# MetronomeSMD.net
KiCad netlist of a schematic drawn in EAGLE
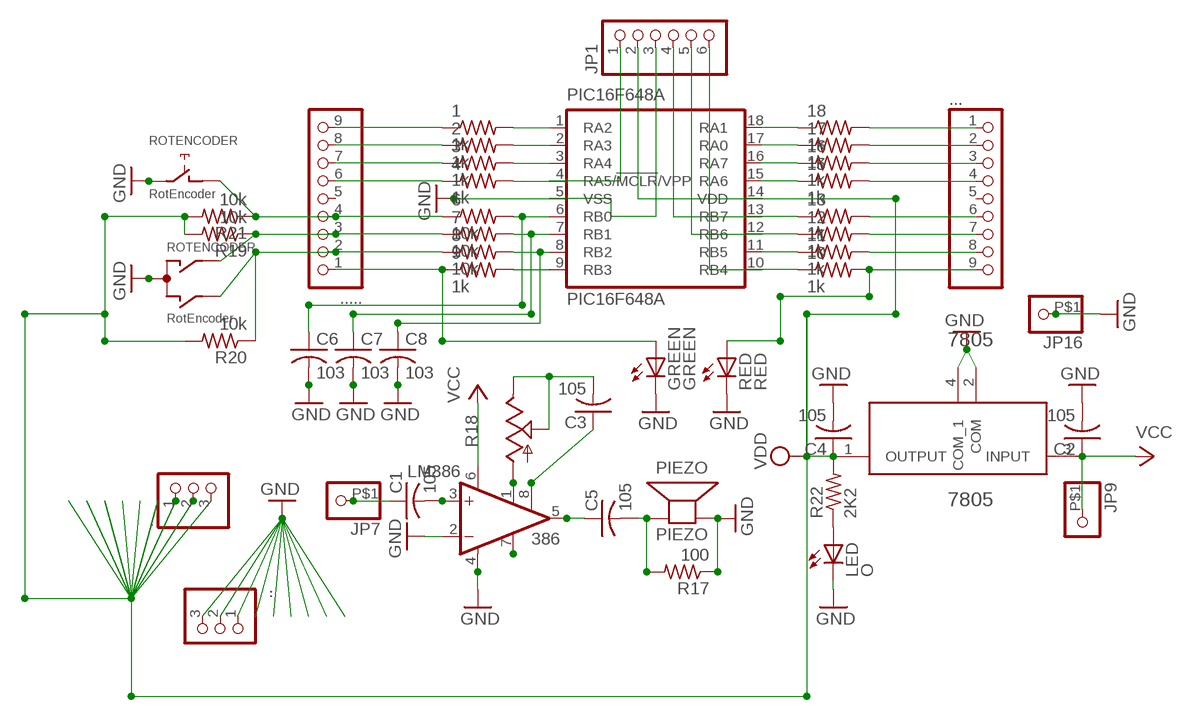
[diagram p0: schematic, sheet 1]

(export (version "E")
  (design (tool "Eeschema 10.0.6"))
  (components
    (comp (ref ".")
      (value "PINHD-1X3CB")
      (footprint "eagle-import:1X03-CLEANBIG")
      (libsource (lib "eagle-import") (part "PINHD-1X3CB"))
    )
    (comp (ref "..")
      (value "PINHD-1X3CB")
      (footprint "eagle-import:1X03-CLEANBIG")
      (libsource (lib "eagle-import") (part "PINHD-1X3CB"))
    )
    (comp (ref "...")
      (value "PINHD-1X9")
      (footprint "eagle-import:1X09-BIG")
      (libsource (lib "eagle-import") (part "PINHD-1X9"))
    )
    (comp (ref ".....")
      (value "PINHD-1X9")
      (footprint "eagle-import:1X09-BIG")
      (libsource (lib "eagle-import") (part "PINHD-1X9"))
    )
    (comp (ref "1")
      (value "1k")
      (footprint "eagle-import:R1206")
      (libsource (lib "eagle-import") (part "R-US_R1206"))
    )
    (comp (ref "2")
      (value "1k")
      (footprint "eagle-import:R1206")
      (libsource (lib "eagle-import") (part "R-US_R1206"))
    )
    (comp (ref "3")
      (value "1k")
      (footprint "eagle-import:R1206")
      (libsource (lib "eagle-import") (part "R-US_R1206"))
    )
    (comp (ref "4")
      (value "1k")
      (footprint "eagle-import:R1206")
      (libsource (lib "eagle-import") (part "R-US_R1206"))
    )
    (comp (ref "6")
      (value "10k")
      (footprint "eagle-import:R1206")
      (libsource (lib "eagle-import") (part "R-US_R1206"))
    )
    (comp (ref "7")
      (value "10k")
      (footprint "eagle-import:R1206")
      (libsource (lib "eagle-import") (part "R-US_R1206"))
    )
    (comp (ref "8")
      (value "10k")
      (footprint "eagle-import:R1206")
      (libsource (lib "eagle-import") (part "R-US_R1206"))
    )
    (comp (ref "9")
      (value "1k")
      (footprint "eagle-import:R1206")
      (libsource (lib "eagle-import") (part "R-US_R1206"))
    )
    (comp (ref "10")
      (value "1k")
      (footprint "eagle-import:R1206")
      (libsource (lib "eagle-import") (part "R-US_R1206"))
    )
    (comp (ref "11")
      (value "1k")
      (footprint "eagle-import:R1206")
      (libsource (lib "eagle-import") (part "R-US_R1206"))
    )
    (comp (ref "12")
      (value "1k")
      (footprint "eagle-import:R1206")
      (libsource (lib "eagle-import") (part "R-US_R1206"))
    )
    (comp (ref "13")
      (value "1k")
      (footprint "eagle-import:R1206")
      (libsource (lib "eagle-import") (part "R-US_R1206"))
    )
    (comp (ref "15")
      (value "1k")
      (footprint "eagle-import:R1206")
      (libsource (lib "eagle-import") (part "R-US_R1206"))
    )
    (comp (ref "16")
      (value "1k")
      (footprint "eagle-import:R1206")
      (libsource (lib "eagle-import") (part "R-US_R1206"))
    )
    (comp (ref "17")
      (value "1k")
      (footprint "eagle-import:R1206")
      (libsource (lib "eagle-import") (part "R-US_R1206"))
    )
    (comp (ref "18")
      (value "1k")
      (footprint "eagle-import:R1206")
      (libsource (lib "eagle-import") (part "R-US_R1206"))
    )
    (comp (ref "7805")
      (value "7805")
      (footprint "eagle-import:SOT150P400X160-4N")
      (fields (field (name "MPN") "UA78L05ACPKG3"))
      (libsource (lib "eagle-import") (part "UA78L05ACPKG3"))
    )
    (comp (ref "C1")
      (value "105")
      (footprint "eagle-import:C1210")
      (libsource (lib "eagle-import") (part "C-USC1210"))
    )
    (comp (ref "C2")
      (value "105")
      (footprint "eagle-import:C1210")
      (libsource (lib "eagle-import") (part "C-USC1210"))
    )
    (comp (ref "C3")
      (value "105")
      (footprint "eagle-import:C1210")
      (libsource (lib "eagle-import") (part "C-USC1210"))
    )
    (comp (ref "C4")
      (value "105")
      (footprint "eagle-import:C1210")
      (libsource (lib "eagle-import") (part "C-USC1210"))
    )
    (comp (ref "C5")
      (value "105")
      (footprint "eagle-import:C1210")
      (libsource (lib "eagle-import") (part "C-USC1210"))
    )
    (comp (ref "C6")
      (value "103")
      (footprint "eagle-import:C1210")
      (libsource (lib "eagle-import") (part "C-USC1210"))
    )
    (comp (ref "C7")
      (value "103")
      (footprint "eagle-import:C1210")
      (libsource (lib "eagle-import") (part "C-USC1210"))
    )
    (comp (ref "C8")
      (value "103")
      (footprint "eagle-import:C1210")
      (libsource (lib "eagle-import") (part "C-USC1210"))
    )
    (comp (ref "GREEN")
      (value "GREEN")
      (footprint "eagle-import:LED5MM")
      (libsource (lib "eagle-import") (part "LED5MM"))
    )
    (comp (ref "JP1")
      (value "PINHD-1X6LOCK")
      (footprint "eagle-import:1X06-BIGLOCK")
      (libsource (lib "eagle-import") (part "PINHD-1X6LOCK"))
    )
    (comp (ref "JP7")
      (value "PINHD-1X1-BIGPOGO")
      (footprint "eagle-import:1X1-BIGPOGO")
      (libsource (lib "eagle-import") (part "PINHD-1X1-BIGPOGO"))
    )
    (comp (ref "JP9")
      (value "PINHD-1X1-BIGPOGO")
      (footprint "eagle-import:1X1-BIGPOGO")
      (libsource (lib "eagle-import") (part "PINHD-1X1-BIGPOGO"))
    )
    (comp (ref "JP16")
      (value "PINHD-1X1-BIGPOGO")
      (footprint "eagle-import:1X1-BIGPOGO")
      (libsource (lib "eagle-import") (part "PINHD-1X1-BIGPOGO"))
    )
    (comp (ref "LED")
      (value "O")
      (footprint "eagle-import:CHIPLED_1206")
      (libsource (lib "eagle-import") (part "LEDCHIPLED_1206"))
    )
    (comp (ref "LM386")
      (value "386")
      (footprint "eagle-import:SO08")
      (libsource (lib "eagle-import") (part "LM386?-M1"))
    )
    (comp (ref "PIC16F648A")
      (value "PIC16F648A")
      (footprint "eagle-import:DIL18")
      (libsource (lib "eagle-import") (part "PIC16F1826/27P"))
    )
    (comp (ref "PIEZO")
      (value "PIEZO")
      (footprint "eagle-import:PS12")
      (libsource (lib "eagle-import") (part "SPEAKER/PS12"))
    )
    (comp (ref "R17")
      (value "100")
      (footprint "eagle-import:R1206")
      (libsource (lib "eagle-import") (part "R-US_R1206"))
    )
    (comp (ref "R18")
      (value "TRIM_US-RJ9W")
      (footprint "eagle-import:RJ9W")
      (libsource (lib "eagle-import") (part "TRIM_US-RJ9W"))
    )
    (comp (ref "R19")
      (value "10k")
      (footprint "eagle-import:R1206")
      (libsource (lib "eagle-import") (part "R-US_R1206"))
    )
    (comp (ref "R20")
      (value "10k")
      (footprint "eagle-import:R1206")
      (libsource (lib "eagle-import") (part "R-US_R1206"))
    )
    (comp (ref "R21")
      (value "10k")
      (footprint "eagle-import:R1206")
      (libsource (lib "eagle-import") (part "R-US_R1206"))
    )
    (comp (ref "R22")
      (value "2K2")
      (footprint "eagle-import:R1206")
      (libsource (lib "eagle-import") (part "R-US_R1206"))
    )
    (comp (ref "RED")
      (value "RED")
      (footprint "eagle-import:LED5MM")
      (libsource (lib "eagle-import") (part "LED5MM"))
    )
    (comp (ref "ROTENCODER")
      (value "RotEncoder")
      (footprint "eagle-import:ALPS_EC12E_SW")
      (fields (field (name "MPN") "EC12E2424407"))
      (libsource (lib "eagle-import") (part "EC12E_SW"))
    )
  )
  (nets
    (net (code "1") (name "GND") (class "Default")
      (node (ref "..") (pin "1") (pinfunction "1_1") (pintype "passive"))
      (node (ref "..") (pin "2") (pinfunction "2_2") (pintype "passive"))
      (node (ref "..") (pin "3") (pinfunction "3_3") (pintype "passive"))
      (node (ref "7805") (pin "2") (pinfunction "COM_2") (pintype "power_in"))
      (node (ref "7805") (pin "4") (pinfunction "COM_1_4") (pintype "power_in"))
      (node (ref "C2") (pin "2") (pinfunction "2_2") (pintype "passive"))
      (node (ref "C4") (pin "2") (pinfunction "2_2") (pintype "passive"))
      (node (ref "C6") (pin "2") (pinfunction "2_2") (pintype "passive"))
      (node (ref "C7") (pin "2") (pinfunction "2_2") (pintype "passive"))
      (node (ref "C8") (pin "2") (pinfunction "2_2") (pintype "passive"))
      (node (ref "GREEN") (pin "K") (pinfunction "C_K") (pintype "passive"))
      (node (ref "JP1") (pin "3") (pinfunction "3_3") (pintype "passive"))
      (node (ref "JP16") (pin "P$1") (pinfunction "1_P$1") (pintype "passive"))
      (node (ref "LED") (pin "C") (pinfunction "C_C") (pintype "passive"))
      (node (ref "LM386") (pin "2") (pinfunction "-IN_2") (pintype "input"))
      (node (ref "LM386") (pin "4") (pinfunction "GND_4") (pintype "power_in"))
      (node (ref "PIC16F648A") (pin "5") (pinfunction "VSS_5") (pintype "power_in"))
      (node (ref "PIEZO") (pin "P$2") (pinfunction "-_P$2") (pintype "passive"))
      (node (ref "R17") (pin "1") (pinfunction "1_1") (pintype "passive"))
      (node (ref "RED") (pin "K") (pinfunction "C_K") (pintype "passive"))
      (node (ref "ROTENCODER") (pin "C") (pinfunction "C_C") (pintype "passive"))
      (node (ref "ROTENCODER") (pin "E") (pinfunction "2_E") (pintype "passive"))
    )
    (net (code "2") (name "Net-(...-Pad1)") (class "Default")
      (node (ref "...") (pin "1") (pinfunction "1_1") (pintype "passive"))
      (node (ref "18") (pin "2") (pinfunction "2_2") (pintype "passive"))
    )
    (net (code "3") (name "Net-(...-Pad2)") (class "Default")
      (node (ref "...") (pin "2") (pinfunction "2_2") (pintype "passive"))
      (node (ref "17") (pin "2") (pinfunction "2_2") (pintype "passive"))
    )
    (net (code "4") (name "Net-(...-Pad3)") (class "Default")
      (node (ref "...") (pin "3") (pinfunction "3_3") (pintype "passive"))
      (node (ref "16") (pin "2") (pinfunction "2_2") (pintype "passive"))
    )
    (net (code "5") (name "Net-(...-Pad4)") (class "Default")
      (node (ref "...") (pin "4") (pinfunction "4_4") (pintype "passive"))
      (node (ref "15") (pin "2") (pinfunction "2_2") (pintype "passive"))
    )
    (net (code "6") (name "Net-(...-Pad6)") (class "Default")
      (node (ref "...") (pin "6") (pinfunction "6_6") (pintype "passive"))
      (node (ref "13") (pin "2") (pinfunction "2_2") (pintype "passive"))
    )
    (net (code "7") (name "Net-(...-Pad7)") (class "Default")
      (node (ref "...") (pin "7") (pinfunction "7_7") (pintype "passive"))
      (node (ref "12") (pin "2") (pinfunction "2_2") (pintype "passive"))
    )
    (net (code "8") (name "Net-(...-Pad8)") (class "Default")
      (node (ref "...") (pin "8") (pinfunction "8_8") (pintype "passive"))
      (node (ref "11") (pin "2") (pinfunction "2_2") (pintype "passive"))
    )
    (net (code "9") (name "Net-(...-Pad9)") (class "Default")
      (node (ref "...") (pin "9") (pinfunction "9_9") (pintype "passive"))
      (node (ref "10") (pin "2") (pinfunction "2_2") (pintype "passive"))
      (node (ref "RED") (pin "A") (pinfunction "A_A") (pintype "passive"))
    )
    (net (code "10") (name "Net-(.....-Pad1)") (class "Default")
      (node (ref ".....") (pin "1") (pinfunction "1_1") (pintype "passive"))
      (node (ref "9") (pin "1") (pinfunction "1_1") (pintype "passive"))
      (node (ref "GREEN") (pin "A") (pinfunction "A_A") (pintype "passive"))
    )
    (net (code "11") (name "Net-(.....-Pad2)") (class "Default")
      (node (ref ".....") (pin "2") (pinfunction "2_2") (pintype "passive"))
      (node (ref "8") (pin "1") (pinfunction "1_1") (pintype "passive"))
      (node (ref "R20") (pin "1") (pinfunction "1_1") (pintype "passive"))
      (node (ref "ROTENCODER") (pin "B") (pinfunction "B_B") (pintype "passive"))
    )
    (net (code "12") (name "Net-(.....-Pad3)") (class "Default")
      (node (ref ".....") (pin "3") (pinfunction "3_3") (pintype "passive"))
      (node (ref "7") (pin "1") (pinfunction "1_1") (pintype "passive"))
      (node (ref "R19") (pin "1") (pinfunction "1_1") (pintype "passive"))
      (node (ref "ROTENCODER") (pin "A") (pinfunction "A_A") (pintype "passive"))
    )
    (net (code "13") (name "Net-(.....-Pad6)") (class "Default")
      (node (ref ".....") (pin "6") (pinfunction "6_6") (pintype "passive"))
      (node (ref "4") (pin "1") (pinfunction "1_1") (pintype "passive"))
    )
    (net (code "14") (name "Net-(.....-Pad7)") (class "Default")
      (node (ref ".....") (pin "7") (pinfunction "7_7") (pintype "passive"))
      (node (ref "3") (pin "1") (pinfunction "1_1") (pintype "passive"))
    )
    (net (code "15") (name "Net-(.....-Pad8)") (class "Default")
      (node (ref ".....") (pin "8") (pinfunction "8_8") (pintype "passive"))
      (node (ref "2") (pin "1") (pinfunction "1_1") (pintype "passive"))
    )
    (net (code "16") (name "Net-(.....-Pad9)") (class "Default")
      (node (ref ".....") (pin "9") (pinfunction "9_9") (pintype "passive"))
      (node (ref "1") (pin "1") (pinfunction "1_1") (pintype "passive"))
    )
    (net (code "17") (name "Net-(C3-Pad1)") (class "Default")
      (node (ref "C3") (pin "1") (pinfunction "1_1") (pintype "passive"))
      (node (ref "LM386") (pin "8") (pinfunction "GAIN_8") (pintype "passive"))
    )
    (net (code "18") (name "Net-(C3-Pad2)") (class "Default")
      (node (ref "C3") (pin "2") (pinfunction "2_2") (pintype "passive"))
      (node (ref "R18") (pin "E") (pinfunction "E_E") (pintype "passive"))
      (node (ref "R18") (pin "S") (pinfunction "S_S") (pintype "passive"))
    )
    (net (code "19") (name "Net-(JP7-1)") (class "Default")
      (node (ref "C1") (pin "1") (pinfunction "1_1") (pintype "passive"))
      (node (ref "JP7") (pin "P$1") (pinfunction "1_P$1") (pintype "passive"))
    )
    (net (code "20") (name "Net-(LED-PadA)") (class "Default")
      (node (ref "LED") (pin "A") (pinfunction "A_A") (pintype "passive"))
      (node (ref "R22") (pin "1") (pinfunction "1_1") (pintype "passive"))
    )
    (net (code "21") (name "Net-(LM386-+IN)") (class "Default")
      (node (ref "C1") (pin "2") (pinfunction "2_2") (pintype "passive"))
      (node (ref "LM386") (pin "3") (pinfunction "+IN_3") (pintype "input"))
    )
    (net (code "22") (name "Net-(LM386-GAIN-Pad1)") (class "Default")
      (node (ref "LM386") (pin "1") (pinfunction "GAIN_1") (pintype "passive"))
      (node (ref "R18") (pin "A") (pinfunction "A_A") (pintype "passive"))
    )
    (net (code "23") (name "Net-(LM386-OUT)") (class "Default")
      (node (ref "C5") (pin "1") (pinfunction "1_1") (pintype "passive"))
      (node (ref "LM386") (pin "5") (pinfunction "OUT_5") (pintype "output"))
    )
    (net (code "24") (name "Net-(PIC16F648A-RA0)") (class "Default")
      (node (ref "17") (pin "1") (pinfunction "1_1") (pintype "passive"))
      (node (ref "PIC16F648A") (pin "17") (pinfunction "RA0_17") (pintype "bidirectional"))
    )
    (net (code "25") (name "Net-(PIC16F648A-RA1)") (class "Default")
      (node (ref "18") (pin "1") (pinfunction "1_1") (pintype "passive"))
      (node (ref "PIC16F648A") (pin "18") (pinfunction "RA1_18") (pintype "bidirectional"))
    )
    (net (code "26") (name "Net-(PIC16F648A-RA2)") (class "Default")
      (node (ref "1") (pin "2") (pinfunction "2_2") (pintype "passive"))
      (node (ref "PIC16F648A") (pin "1") (pinfunction "RA2_1") (pintype "bidirectional"))
    )
    (net (code "27") (name "Net-(PIC16F648A-RA3)") (class "Default")
      (node (ref "2") (pin "2") (pinfunction "2_2") (pintype "passive"))
      (node (ref "PIC16F648A") (pin "2") (pinfunction "RA3_2") (pintype "bidirectional"))
    )
    (net (code "28") (name "Net-(PIC16F648A-RA4)") (class "Default")
      (node (ref "3") (pin "2") (pinfunction "2_2") (pintype "passive"))
      (node (ref "PIC16F648A") (pin "3") (pinfunction "RA4_3") (pintype "bidirectional"))
    )
    (net (code "29") (name "Net-(PIC16F648A-RA5{slash}~{MCLR}{slash}VPP)") (class "Default")
      (node (ref "4") (pin "2") (pinfunction "2_2") (pintype "passive"))
      (node (ref "JP1") (pin "1") (pinfunction "1_1") (pintype "passive"))
      (node (ref "PIC16F648A") (pin "4") (pinfunction "RA5/~{MCLR}/VPP_4") (pintype "bidirectional"))
    )
    (net (code "30") (name "Net-(PIC16F648A-RA6)") (class "Default")
      (node (ref "15") (pin "1") (pinfunction "1_1") (pintype "passive"))
      (node (ref "PIC16F648A") (pin "15") (pinfunction "RA6_15") (pintype "bidirectional"))
    )
    (net (code "31") (name "Net-(PIC16F648A-RA7)") (class "Default")
      (node (ref "16") (pin "1") (pinfunction "1_1") (pintype "passive"))
      (node (ref "PIC16F648A") (pin "16") (pinfunction "RA7_16") (pintype "bidirectional"))
    )
    (net (code "32") (name "Net-(PIC16F648A-RB0)") (class "Default")
      (node (ref "6") (pin "2") (pinfunction "2_2") (pintype "passive"))
      (node (ref "C6") (pin "1") (pinfunction "1_1") (pintype "passive"))
      (node (ref "PIC16F648A") (pin "6") (pinfunction "RB0_6") (pintype "bidirectional"))
    )
    (net (code "33") (name "Net-(PIC16F648A-RB1)") (class "Default")
      (node (ref "7") (pin "2") (pinfunction "2_2") (pintype "passive"))
      (node (ref "C7") (pin "1") (pinfunction "1_1") (pintype "passive"))
      (node (ref "PIC16F648A") (pin "7") (pinfunction "RB1_7") (pintype "bidirectional"))
    )
    (net (code "34") (name "Net-(PIC16F648A-RB2)") (class "Default")
      (node (ref "8") (pin "2") (pinfunction "2_2") (pintype "passive"))
      (node (ref "C8") (pin "1") (pinfunction "1_1") (pintype "passive"))
      (node (ref "PIC16F648A") (pin "8") (pinfunction "RB2_8") (pintype "bidirectional"))
    )
    (net (code "35") (name "Net-(PIC16F648A-RB3)") (class "Default")
      (node (ref "9") (pin "2") (pinfunction "2_2") (pintype "passive"))
      (node (ref "PIC16F648A") (pin "9") (pinfunction "RB3_9") (pintype "bidirectional"))
    )
    (net (code "36") (name "Net-(PIC16F648A-RB4)") (class "Default")
      (node (ref "10") (pin "1") (pinfunction "1_1") (pintype "passive"))
      (node (ref "JP1") (pin "6") (pinfunction "6_6") (pintype "passive"))
      (node (ref "PIC16F648A") (pin "10") (pinfunction "RB4_10") (pintype "bidirectional"))
    )
    (net (code "37") (name "Net-(PIC16F648A-RB5)") (class "Default")
      (node (ref "11") (pin "1") (pinfunction "1_1") (pintype "passive"))
      (node (ref "PIC16F648A") (pin "11") (pinfunction "RB5_11") (pintype "bidirectional"))
    )
    (net (code "38") (name "Net-(PIC16F648A-RB6)") (class "Default")
      (node (ref "12") (pin "1") (pinfunction "1_1") (pintype "passive"))
      (node (ref "JP1") (pin "5") (pinfunction "5_5") (pintype "passive"))
      (node (ref "PIC16F648A") (pin "12") (pinfunction "RB6_12") (pintype "bidirectional"))
    )
    (net (code "39") (name "Net-(PIC16F648A-RB7)") (class "Default")
      (node (ref "13") (pin "1") (pinfunction "1_1") (pintype "passive"))
      (node (ref "JP1") (pin "4") (pinfunction "4_4") (pintype "passive"))
      (node (ref "PIC16F648A") (pin "13") (pinfunction "RB7_13") (pintype "bidirectional"))
    )
    (net (code "40") (name "Net-(PIEZO-+)") (class "Default")
      (node (ref "C5") (pin "2") (pinfunction "2_2") (pintype "passive"))
      (node (ref "PIEZO") (pin "P$1") (pinfunction "+_P$1") (pintype "passive"))
      (node (ref "R17") (pin "2") (pinfunction "2_2") (pintype "passive"))
    )
    (net (code "41") (name "Net-(ROTENCODERB-1)") (class "Default")
      (node (ref ".....") (pin "4") (pinfunction "4_4") (pintype "passive"))
      (node (ref "6") (pin "1") (pinfunction "1_1") (pintype "passive"))
      (node (ref "R21") (pin "1") (pinfunction "1_1") (pintype "passive"))
      (node (ref "ROTENCODER") (pin "D") (pinfunction "1_D") (pintype "passive"))
    )
    (net (code "42") (name "VCC") (class "Default")
      (node (ref "7805") (pin "3") (pinfunction "INPUT_3") (pintype "input"))
      (node (ref "C2") (pin "1") (pinfunction "1_1") (pintype "passive"))
      (node (ref "JP9") (pin "P$1") (pinfunction "1_P$1") (pintype "passive"))
      (node (ref "LM386") (pin "6") (pinfunction "VS_6") (pintype "power_in"))
    )
    (net (code "43") (name "VDD") (class "Default")
      (node (ref ".") (pin "1") (pinfunction "1_1") (pintype "passive"))
      (node (ref ".") (pin "2") (pinfunction "2_2") (pintype "passive"))
      (node (ref ".") (pin "3") (pinfunction "3_3") (pintype "passive"))
      (node (ref "7805") (pin "1") (pinfunction "OUTPUT_1") (pintype "output"))
      (node (ref "C4") (pin "1") (pinfunction "1_1") (pintype "passive"))
      (node (ref "JP1") (pin "2") (pinfunction "2_2") (pintype "passive"))
      (node (ref "PIC16F648A") (pin "14") (pinfunction "VDD_14") (pintype "power_in"))
      (node (ref "R19") (pin "2") (pinfunction "2_2") (pintype "passive"))
      (node (ref "R20") (pin "2") (pinfunction "2_2") (pintype "passive"))
      (node (ref "R21") (pin "2") (pinfunction "2_2") (pintype "passive"))
      (node (ref "R22") (pin "2") (pinfunction "2_2") (pintype "passive"))
    )
    (net (code "44") (name "unconnected-(...-Pad5)") (class "Default")
      (node (ref "...") (pin "5") (pinfunction "5_5") (pintype "passive"))
    )
    (net (code "45") (name "unconnected-(.....-Pad5)") (class "Default")
      (node (ref ".....") (pin "5") (pinfunction "5_5") (pintype "passive"))
    )
    (net (code "46") (name "unconnected-(LM386-BYPASS-Pad7)") (class "Default")
      (node (ref "LM386") (pin "7") (pinfunction "BYPASS_7") (pintype "passive"))
    )
  )
)
